# Sheet1.net
KiCad netlist of a schematic drawn in Altium Designer
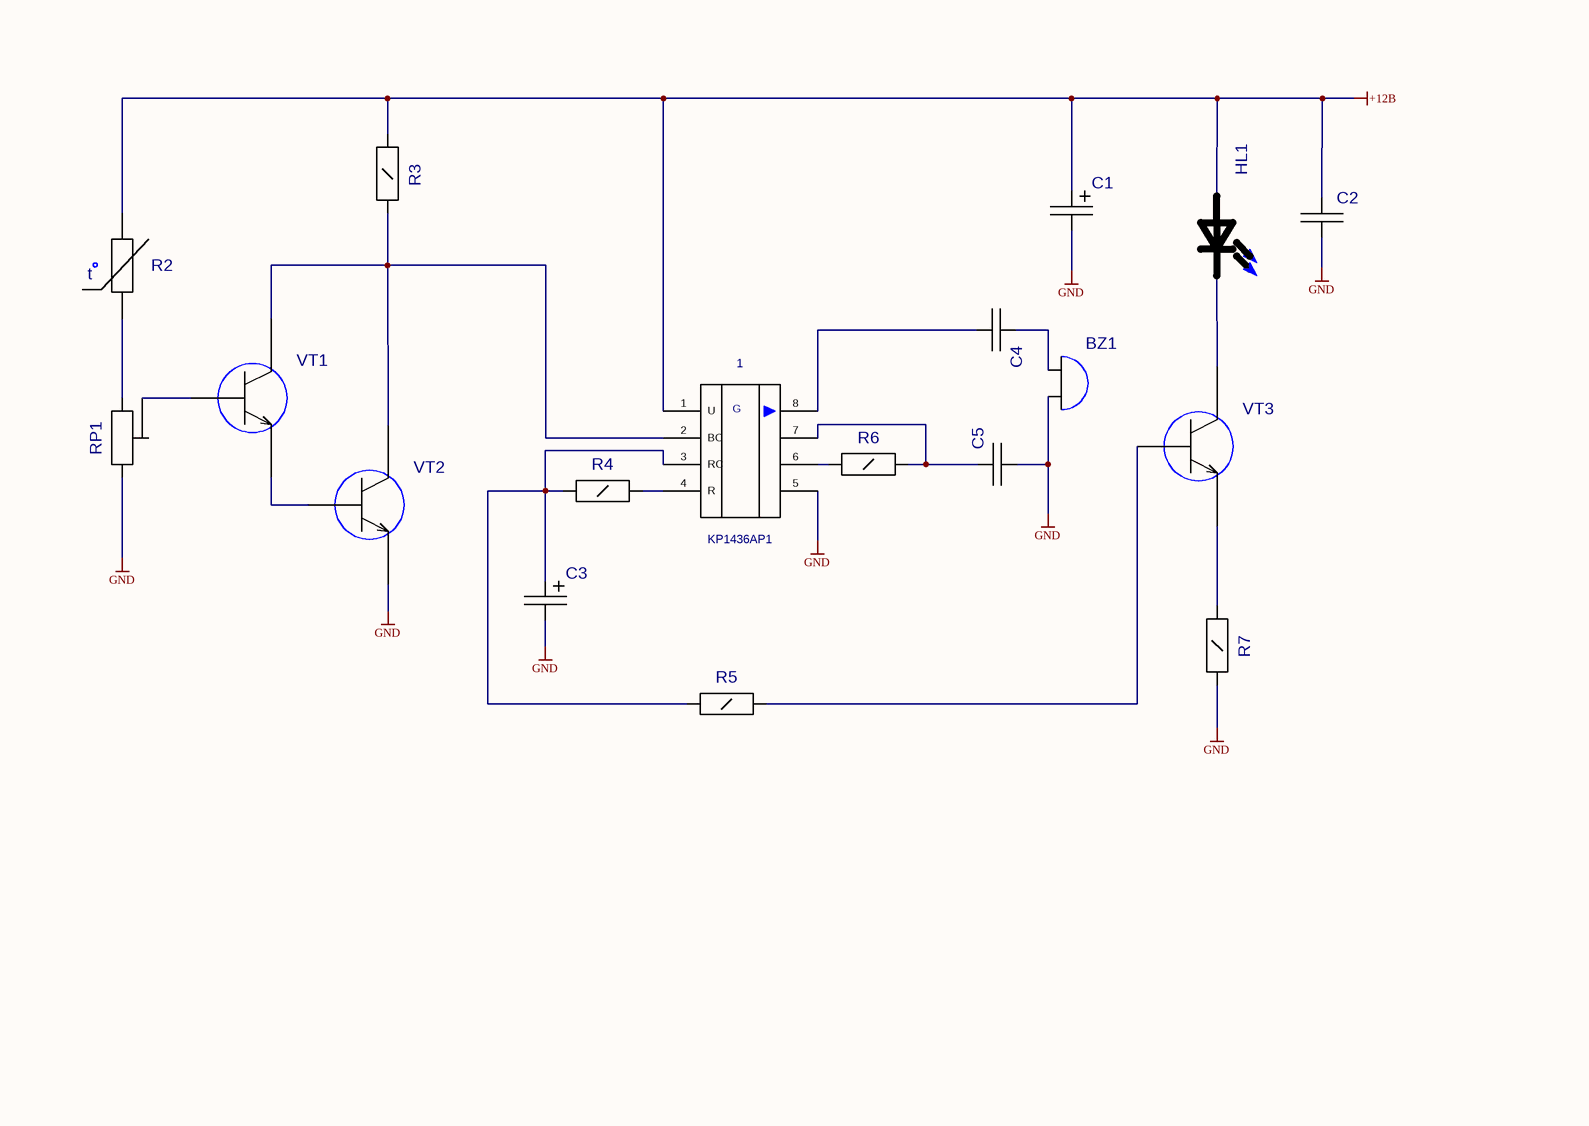
[diagram p0: Sheet1.SCHDOC]

(export (version "E")
  (design (tool "Eeschema 10.0.6"))
  (components
    (comp (ref "1") (value "KP1436AP1") (footprint "KP1436AP1") (libsource (lib "*") (part "KP1436AP1")))
    (comp (ref "BZ1") (value "ZUM1") (footprint "ZUM1") (libsource (lib "*") (part "ZUM1")))
    (comp (ref "C1") (value "CE3528-B") (footprint "CE3528-B") (libsource (lib "*") (part "CE3528-B")))
    (comp (ref "C2") (value "CC0603") (footprint "CC0603") (libsource (lib "*") (part "CC0603")))
    (comp (ref "C3") (value "CE3528-B") (footprint "CE3528-B") (libsource (lib "*") (part "CE3528-B")))
    (comp (ref "C4") (value "CC0603") (footprint "CC0603") (libsource (lib "*") (part "CC0603")))
    (comp (ref "C5") (value "CC0603") (footprint "CC0603") (libsource (lib "*") (part "CC0603")))
    (comp (ref "HL1") (value "3528") (footprint "3528") (libsource (lib "*") (part "3528")))
    (comp (ref "R2")
      (value "B57861S0103F040")
      (footprint "B57861")
      (fields (field (name "AUTHOR") "pcbdesigner.ru"))
      (libsource (lib "*") (part "B57861S0103F040"))
    )
    (comp (ref "R3")
      (value "C2-33H-0.25W_OLD_UGO")
      (footprint "C2-33H-0.25W")
      (fields (field (name "AUTOR") "pcbdesigner.ru"))
      (libsource (lib "*") (part "C2-33H-0.25W_OLD_UGO"))
    )
    (comp (ref "R4")
      (value "C2-33H-0.25W_OLD_UGO")
      (footprint "C2-33H-0.25W")
      (fields (field (name "AUTOR") "pcbdesigner.ru"))
      (libsource (lib "*") (part "C2-33H-0.25W_OLD_UGO"))
    )
    (comp (ref "R5")
      (value "C2-33H-0.25W_OLD_UGO")
      (footprint "C2-33H-0.25W")
      (fields (field (name "AUTOR") "pcbdesigner.ru"))
      (libsource (lib "*") (part "C2-33H-0.25W_OLD_UGO"))
    )
    (comp (ref "R6")
      (value "C2-33H-0.25W_OLD_UGO")
      (footprint "C2-33H-0.25W")
      (fields (field (name "AUTOR") "pcbdesigner.ru"))
      (libsource (lib "*") (part "C2-33H-0.25W_OLD_UGO"))
    )
    (comp (ref "R7")
      (value "C2-33H-0.25W_OLD_UGO")
      (footprint "C2-33H-0.25W")
      (fields (field (name "AUTOR") "pcbdesigner.ru"))
      (libsource (lib "*") (part "C2-33H-0.25W_OLD_UGO"))
    )
    (comp (ref "RP1") (value "3006W") (footprint "3006P") (libsource (lib "*") (part "3006W")))
    (comp (ref "VT1") (value "2N4401") (footprint "TO-92-1") (libsource (lib "*") (part "2N4401")))
    (comp (ref "VT2") (value "2N4401") (footprint "TO-92-1") (libsource (lib "*") (part "2N4401")))
    (comp (ref "VT3") (value "2N4401") (footprint "TO-92-1") (libsource (lib "*") (part "2N4401")))
  )
  (nets
    (net (code "1") (name "+12B") (class "Default")
      (node (ref "1") (pin "1") (pinfunction "U_1") (pintype "passive"))
      (node (ref "C1") (pin "1") (pinfunction "i/o_1") (pintype "passive"))
      (node (ref "C2") (pin "2") (pinfunction "i/o_2") (pintype "passive"))
      (node (ref "HL1") (pin "A") (pinfunction "A_A") (pintype "passive"))
      (node (ref "R2") (pin "2") (pinfunction "2_2") (pintype "passive"))
      (node (ref "R3") (pin "1") (pinfunction "1_1") (pintype "passive"))
    )
    (net (code "2") (name "GND") (class "Default")
      (node (ref "1") (pin "5") (pintype "passive"))
      (node (ref "BZ1") (pin "2") (pinfunction "2_2") (pintype "passive"))
      (node (ref "C1") (pin "2") (pinfunction "i/o1_2") (pintype "passive"))
      (node (ref "C2") (pin "1") (pinfunction "i/o1_1") (pintype "passive"))
      (node (ref "C3") (pin "2") (pinfunction "i/o1_2") (pintype "passive"))
      (node (ref "C5") (pin "1") (pinfunction "i/o1_1") (pintype "passive"))
      (node (ref "R7") (pin "2") (pinfunction "2_2") (pintype "passive"))
      (node (ref "RP1") (pin "1") (pinfunction "1_1") (pintype "passive"))
      (node (ref "VT2") (pin "1") (pinfunction "E_1") (pintype "passive"))
    )
    (net (code "3") (name "Net-(1-BC)") (class "Default")
      (node (ref "1") (pin "2") (pinfunction "BC_2") (pintype "passive"))
      (node (ref "R3") (pin "2") (pinfunction "2_2") (pintype "passive"))
      (node (ref "VT1") (pin "3") (pinfunction "K_3") (pintype "passive"))
      (node (ref "VT2") (pin "3") (pinfunction "K_3") (pintype "passive"))
    )
    (net (code "4") (name "Net-(1-Pad6)") (class "Default")
      (node (ref "1") (pin "6") (pintype "passive"))
      (node (ref "R6") (pin "1") (pinfunction "1_1") (pintype "passive"))
    )
    (net (code "5") (name "Net-(1-R)") (class "Default")
      (node (ref "1") (pin "4") (pinfunction "R_4") (pintype "passive"))
      (node (ref "R4") (pin "2") (pinfunction "2_2") (pintype "passive"))
    )
    (net (code "6") (name "Net-(1-RC)") (class "Default")
      (node (ref "1") (pin "3") (pinfunction "RC_3") (pintype "passive"))
      (node (ref "C3") (pin "1") (pinfunction "i/o_1") (pintype "passive"))
      (node (ref "R4") (pin "1") (pinfunction "1_1") (pintype "passive"))
      (node (ref "R5") (pin "1") (pinfunction "1_1") (pintype "passive"))
    )
    (net (code "7") (name "Net-(C4-i{slash}o)") (class "Default")
      (node (ref "BZ1") (pin "1") (pinfunction "1_1") (pintype "passive"))
      (node (ref "C4") (pin "2") (pinfunction "i/o_2") (pintype "passive"))
    )
    (net (code "8") (name "Net-(C4-i{slash}o1)") (class "Default")
      (node (ref "1") (pin "8") (pintype "passive"))
      (node (ref "C4") (pin "1") (pinfunction "i/o1_1") (pintype "passive"))
    )
    (net (code "9") (name "Net-(C5-i{slash}o)") (class "Default")
      (node (ref "1") (pin "7") (pintype "passive"))
      (node (ref "C5") (pin "2") (pinfunction "i/o_2") (pintype "passive"))
      (node (ref "R6") (pin "2") (pinfunction "2_2") (pintype "passive"))
    )
    (net (code "10") (name "Net-(R2-Pad1)") (class "Default")
      (node (ref "R2") (pin "1") (pinfunction "1_1") (pintype "passive"))
      (node (ref "RP1") (pin "3") (pinfunction "3_3") (pintype "passive"))
    )
    (net (code "11") (name "Net-(VT1-B)") (class "Default")
      (node (ref "RP1") (pin "2") (pinfunction "2_2") (pintype "passive"))
      (node (ref "VT1") (pin "2") (pinfunction "B_2") (pintype "passive"))
    )
    (net (code "12") (name "Net-(VT1-E)") (class "Default")
      (node (ref "VT1") (pin "1") (pinfunction "E_1") (pintype "passive"))
      (node (ref "VT2") (pin "2") (pinfunction "B_2") (pintype "passive"))
    )
    (net (code "13") (name "Net-(VT3-B)") (class "Default")
      (node (ref "R5") (pin "2") (pinfunction "2_2") (pintype "passive"))
      (node (ref "VT3") (pin "2") (pinfunction "B_2") (pintype "passive"))
    )
    (net (code "14") (name "Net-(VT3-E)") (class "Default")
      (node (ref "R7") (pin "1") (pinfunction "1_1") (pintype "passive"))
      (node (ref "VT3") (pin "1") (pinfunction "E_1") (pintype "passive"))
    )
    (net (code "15") (name "Net-(VT3-K)") (class "Default")
      (node (ref "HL1") (pin "K") (pinfunction "K_K") (pintype "passive"))
      (node (ref "VT3") (pin "3") (pinfunction "K_3") (pintype "passive"))
    )
  )
)
